# MPR121-Breakout.net
KiCad netlist of a schematic drawn in EAGLE
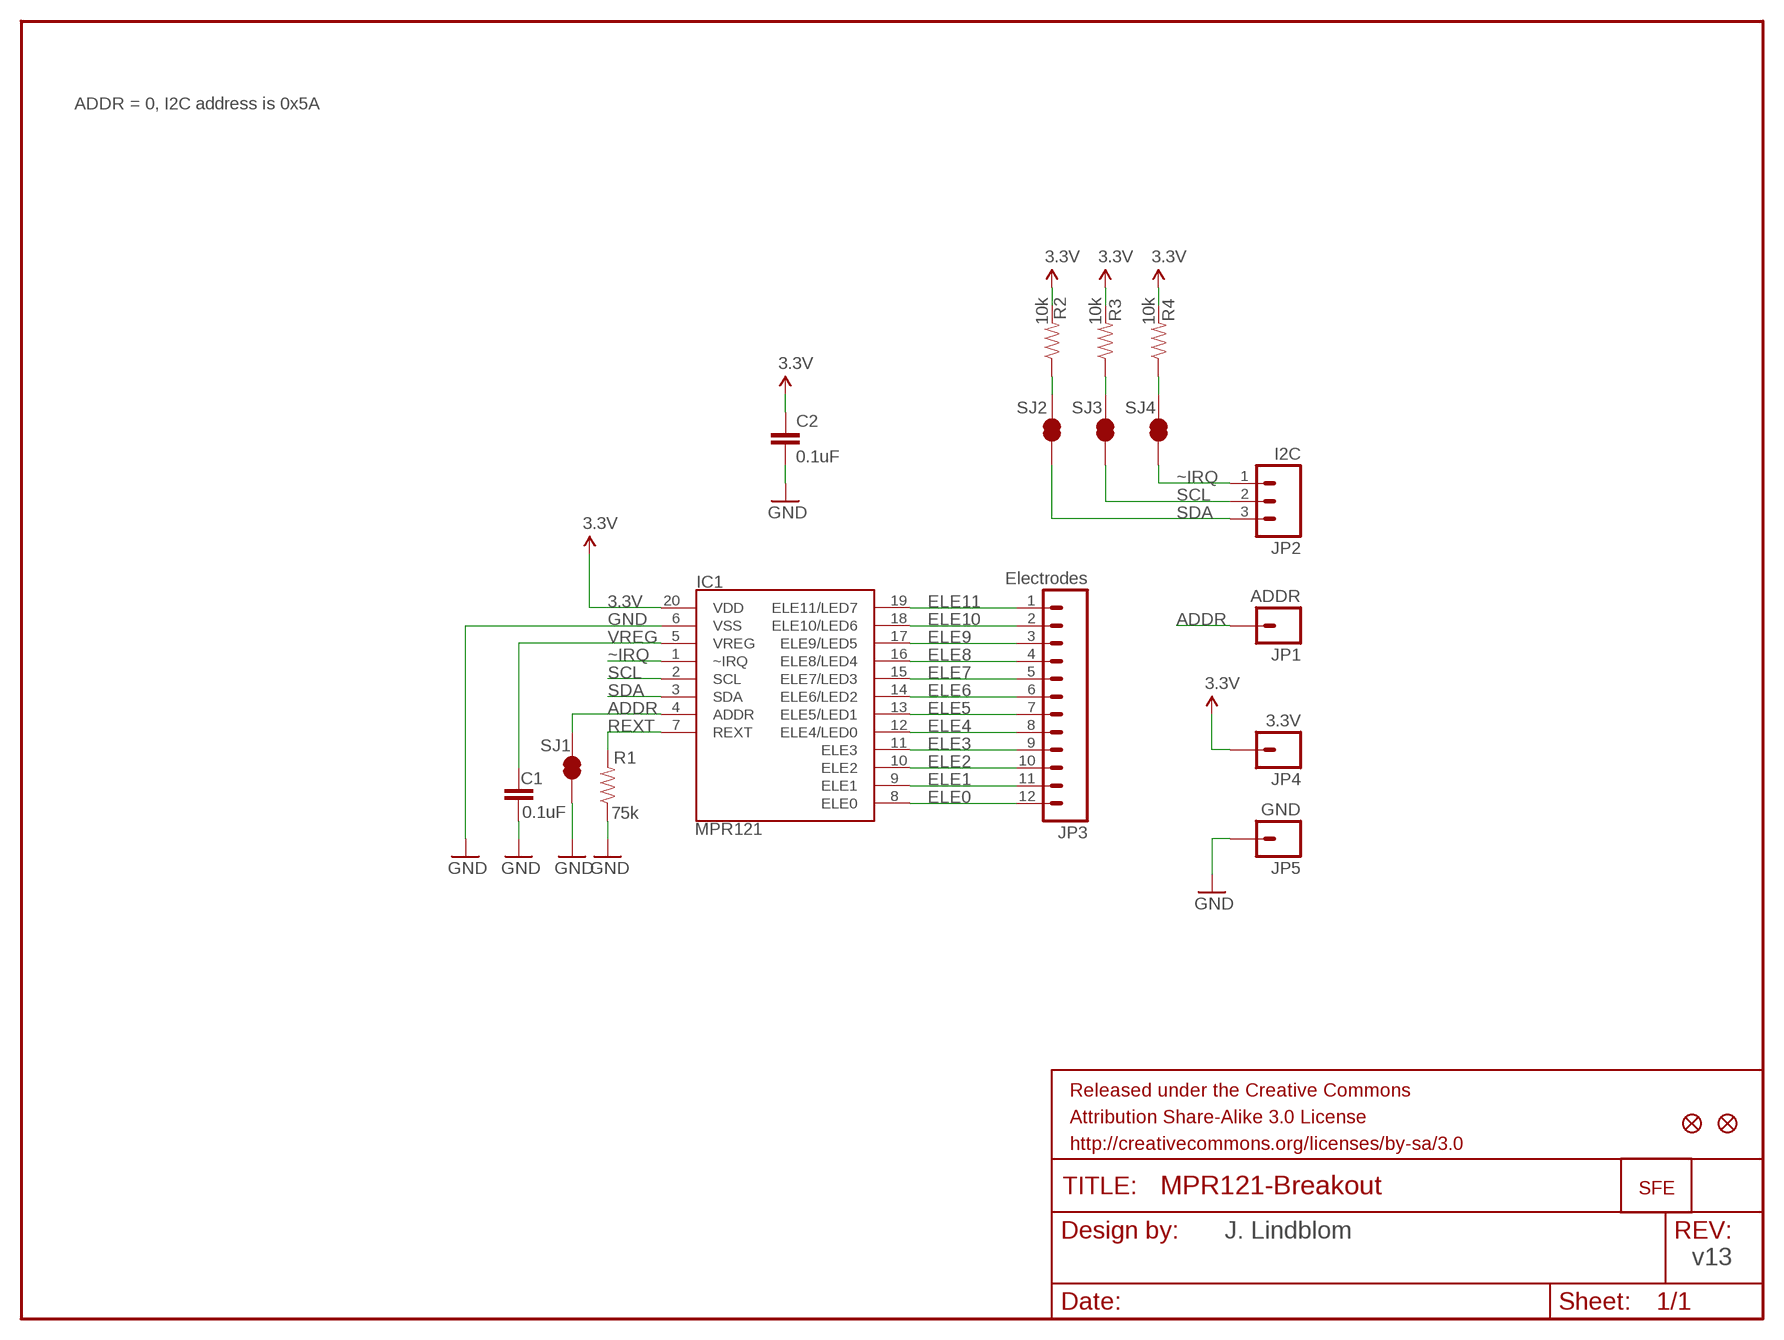
[diagram p0: schematic, sheet 1]

(export (version "E")
  (design (tool "Eeschema 10.0.6"))
  (components
    (comp (ref "C1")
      (value "0.1uF")
      (footprint "eagle-import:0603-CAP")
      (libsource (lib "eagle-import") (part "CAP0603-CAP"))
    )
    (comp (ref "C2")
      (value "0.1uF")
      (footprint "eagle-import:0603-CAP")
      (libsource (lib "eagle-import") (part "CAP0603-CAP"))
    )
    (comp (ref "FRAME1")
      (value "FRAME-LETTER")
      (footprint "eagle-import:CREATIVE_COMMONS")
      (libsource (lib "eagle-import") (part "FRAME-LETTER"))
    )
    (comp (ref "IC1")
      (value "MPR121")
      (footprint "eagle-import:QFN-20-0.4MM-V2")
      (libsource (lib "eagle-import") (part "MPR121V2"))
    )
    (comp (ref "JP1")
      (value "ADDR")
      (footprint "eagle-import:1X01")
      (libsource (lib "eagle-import") (part "M01PTH"))
    )
    (comp (ref "JP2")
      (value "I2C")
      (footprint "eagle-import:1X03")
      (libsource (lib "eagle-import") (part "M03PTH"))
    )
    (comp (ref "JP3")
      (value "Electrodes")
      (footprint "eagle-import:1X12")
      (libsource (lib "eagle-import") (part "M12PTH"))
    )
    (comp (ref "JP4")
      (value "3.3V")
      (footprint "eagle-import:1X01")
      (libsource (lib "eagle-import") (part "M01PTH"))
    )
    (comp (ref "JP5")
      (value "GND")
      (footprint "eagle-import:1X01")
      (libsource (lib "eagle-import") (part "M01PTH"))
    )
    (comp (ref "JP7")
      (value "LOGO-SFENEW")
      (footprint "eagle-import:SFE-NEW-WEBLOGO")
      (libsource (lib "eagle-import") (part "LOGO-SFENEW"))
    )
    (comp (ref "JP8")
      (value "FIDUCIAL1X2")
      (footprint "eagle-import:FIDUCIAL-1X2")
      (libsource (lib "eagle-import") (part "FIDUCIAL1X2"))
    )
    (comp (ref "JP9")
      (value "FIDUCIAL1X2")
      (footprint "eagle-import:FIDUCIAL-1X2")
      (libsource (lib "eagle-import") (part "FIDUCIAL1X2"))
    )
    (comp (ref "R1")
      (value "75k")
      (footprint "eagle-import:0603-RES")
      (libsource (lib "eagle-import") (part "RESISTOR0603-RES"))
    )
    (comp (ref "R2")
      (value "10k")
      (footprint "eagle-import:0603-RES")
      (libsource (lib "eagle-import") (part "RESISTOR0603-RES"))
    )
    (comp (ref "R3")
      (value "10k")
      (footprint "eagle-import:0603-RES")
      (libsource (lib "eagle-import") (part "RESISTOR0603-RES"))
    )
    (comp (ref "R4")
      (value "10k")
      (footprint "eagle-import:0603-RES")
      (libsource (lib "eagle-import") (part "RESISTOR0603-RES"))
    )
    (comp (ref "SJ1")
      (value "SOLDERJUMPERTRACE")
      (footprint "eagle-import:SJ_2S-TRACE")
      (libsource (lib "eagle-import") (part "SOLDERJUMPERTRACE"))
    )
    (comp (ref "SJ2")
      (value "SOLDERJUMPERTRACE")
      (footprint "eagle-import:SJ_2S-TRACE")
      (libsource (lib "eagle-import") (part "SOLDERJUMPERTRACE"))
    )
    (comp (ref "SJ3")
      (value "SOLDERJUMPERTRACE")
      (footprint "eagle-import:SJ_2S-TRACE")
      (libsource (lib "eagle-import") (part "SOLDERJUMPERTRACE"))
    )
    (comp (ref "SJ4")
      (value "SOLDERJUMPERTRACE")
      (footprint "eagle-import:SJ_2S-TRACE")
      (libsource (lib "eagle-import") (part "SOLDERJUMPERTRACE"))
    )
  )
  (nets
    (net (code "1") (name "/ADDR") (class "Default")
      (node (ref "IC1") (pin "4") (pinfunction "ADDR_4") (pintype "bidirectional"))
      (node (ref "JP1") (pin "1") (pinfunction "1_1") (pintype "passive"))
      (node (ref "SJ1") (pin "2") (pinfunction "2_2") (pintype "passive"))
    )
    (net (code "2") (name "/ELE0") (class "Default")
      (node (ref "IC1") (pin "8") (pinfunction "ELE0_8") (pintype "bidirectional"))
      (node (ref "JP3") (pin "12") (pinfunction "12_12") (pintype "passive"))
    )
    (net (code "3") (name "/ELE1") (class "Default")
      (node (ref "IC1") (pin "9") (pinfunction "ELE1_9") (pintype "bidirectional"))
      (node (ref "JP3") (pin "11") (pinfunction "11_11") (pintype "passive"))
    )
    (net (code "4") (name "/ELE2") (class "Default")
      (node (ref "IC1") (pin "10") (pinfunction "ELE2_10") (pintype "bidirectional"))
      (node (ref "JP3") (pin "10") (pinfunction "10_10") (pintype "passive"))
    )
    (net (code "5") (name "/ELE3") (class "Default")
      (node (ref "IC1") (pin "11") (pinfunction "ELE3_11") (pintype "bidirectional"))
      (node (ref "JP3") (pin "9") (pinfunction "9_9") (pintype "passive"))
    )
    (net (code "6") (name "/ELE4") (class "Default")
      (node (ref "IC1") (pin "12") (pinfunction "ELE4/LED0_12") (pintype "bidirectional"))
      (node (ref "JP3") (pin "8") (pinfunction "8_8") (pintype "passive"))
    )
    (net (code "7") (name "/ELE5") (class "Default")
      (node (ref "IC1") (pin "13") (pinfunction "ELE5/LED1_13") (pintype "bidirectional"))
      (node (ref "JP3") (pin "7") (pinfunction "7_7") (pintype "passive"))
    )
    (net (code "8") (name "/ELE6") (class "Default")
      (node (ref "IC1") (pin "14") (pinfunction "ELE6/LED2_14") (pintype "bidirectional"))
      (node (ref "JP3") (pin "6") (pinfunction "6_6") (pintype "passive"))
    )
    (net (code "9") (name "/ELE7") (class "Default")
      (node (ref "IC1") (pin "15") (pinfunction "ELE7/LED3_15") (pintype "bidirectional"))
      (node (ref "JP3") (pin "5") (pinfunction "5_5") (pintype "passive"))
    )
    (net (code "10") (name "/ELE8") (class "Default")
      (node (ref "IC1") (pin "16") (pinfunction "ELE8/LED4_16") (pintype "bidirectional"))
      (node (ref "JP3") (pin "4") (pinfunction "4_4") (pintype "passive"))
    )
    (net (code "11") (name "/ELE9") (class "Default")
      (node (ref "IC1") (pin "17") (pinfunction "ELE9/LED5_17") (pintype "bidirectional"))
      (node (ref "JP3") (pin "3") (pinfunction "3_3") (pintype "passive"))
    )
    (net (code "12") (name "/ELE10") (class "Default")
      (node (ref "IC1") (pin "18") (pinfunction "ELE10/LED6_18") (pintype "bidirectional"))
      (node (ref "JP3") (pin "2") (pinfunction "2_2") (pintype "passive"))
    )
    (net (code "13") (name "/ELE11") (class "Default")
      (node (ref "IC1") (pin "19") (pinfunction "ELE11/LED7_19") (pintype "bidirectional"))
      (node (ref "JP3") (pin "1") (pinfunction "1_1") (pintype "passive"))
    )
    (net (code "14") (name "/REXT") (class "Default")
      (node (ref "IC1") (pin "7") (pinfunction "REXT_7") (pintype "bidirectional"))
      (node (ref "R1") (pin "2") (pinfunction "2_2") (pintype "passive"))
    )
    (net (code "15") (name "/SCL") (class "Default")
      (node (ref "IC1") (pin "2") (pinfunction "SCL_2") (pintype "bidirectional"))
      (node (ref "JP2") (pin "2") (pinfunction "2_2") (pintype "passive"))
      (node (ref "SJ3") (pin "1") (pinfunction "1_1") (pintype "passive"))
    )
    (net (code "16") (name "/SDA") (class "Default")
      (node (ref "IC1") (pin "3") (pinfunction "SDA_3") (pintype "bidirectional"))
      (node (ref "JP2") (pin "3") (pinfunction "3_3") (pintype "passive"))
      (node (ref "SJ2") (pin "1") (pinfunction "1_1") (pintype "passive"))
    )
    (net (code "17") (name "/VREG") (class "Default")
      (node (ref "C1") (pin "1") (pinfunction "1_1") (pintype "passive"))
      (node (ref "IC1") (pin "5") (pinfunction "VREG_5") (pintype "bidirectional"))
    )
    (net (code "18") (name "/~{IRQ}") (class "Default")
      (node (ref "IC1") (pin "1") (pinfunction "~{IRQ}_1") (pintype "bidirectional"))
      (node (ref "JP2") (pin "1") (pinfunction "1_1") (pintype "passive"))
      (node (ref "SJ4") (pin "1") (pinfunction "1_1") (pintype "passive"))
    )
    (net (code "19") (name "3.3V") (class "Default")
      (node (ref "C2") (pin "1") (pinfunction "1_1") (pintype "passive"))
      (node (ref "IC1") (pin "20") (pinfunction "VDD_20") (pintype "bidirectional"))
      (node (ref "JP4") (pin "1") (pinfunction "1_1") (pintype "passive"))
      (node (ref "R2") (pin "2") (pinfunction "2_2") (pintype "passive"))
      (node (ref "R3") (pin "2") (pinfunction "2_2") (pintype "passive"))
      (node (ref "R4") (pin "2") (pinfunction "2_2") (pintype "passive"))
    )
    (net (code "20") (name "GND") (class "Default")
      (node (ref "C1") (pin "2") (pinfunction "2_2") (pintype "passive"))
      (node (ref "C2") (pin "2") (pinfunction "2_2") (pintype "passive"))
      (node (ref "IC1") (pin "6") (pinfunction "VSS_6") (pintype "bidirectional"))
      (node (ref "JP5") (pin "1") (pinfunction "1_1") (pintype "passive"))
      (node (ref "R1") (pin "1") (pinfunction "1_1") (pintype "passive"))
      (node (ref "SJ1") (pin "1") (pinfunction "1_1") (pintype "passive"))
    )
    (net (code "21") (name "Net-(R2-Pad1)") (class "Default")
      (node (ref "R2") (pin "1") (pinfunction "1_1") (pintype "passive"))
      (node (ref "SJ2") (pin "2") (pinfunction "2_2") (pintype "passive"))
    )
    (net (code "22") (name "Net-(R3-Pad1)") (class "Default")
      (node (ref "R3") (pin "1") (pinfunction "1_1") (pintype "passive"))
      (node (ref "SJ3") (pin "2") (pinfunction "2_2") (pintype "passive"))
    )
    (net (code "23") (name "Net-(R4-Pad1)") (class "Default")
      (node (ref "R4") (pin "1") (pinfunction "1_1") (pintype "passive"))
      (node (ref "SJ4") (pin "2") (pinfunction "2_2") (pintype "passive"))
    )
  )
)
